# QCopterFC_LED_Sch.net
KiCad netlist of a schematic drawn in Altium Designer
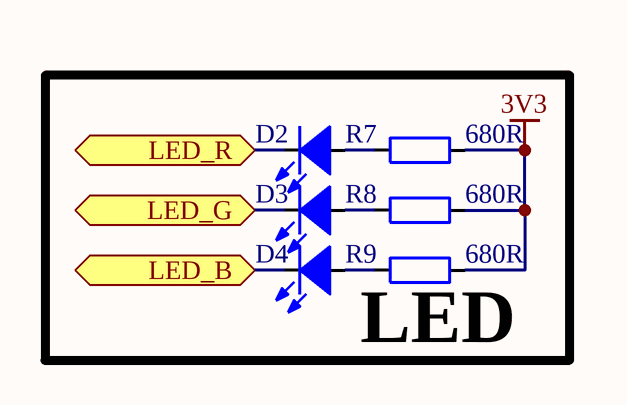
[diagram p0: QCopterFC_LED_Sch.SchDoc]

(export (version "E")
  (design (tool "Eeschema 10.0.6"))
  (components
    (comp (ref "D2")
      (value "LED_0603")
      (footprint "PCB_Active:LED_0603_RED")
      (description "LED")
      (libsource (lib "SCH_Active") (part "LED_0603"))
    )
    (comp (ref "D3")
      (value "LED_0603")
      (footprint "PCB_Active:LED_0603_GREEN")
      (description "LED")
      (libsource (lib "SCH_Active") (part "LED_0603"))
    )
    (comp (ref "D4")
      (value "LED_0603")
      (footprint "PCB_Active:LED_0603_BLUE")
      (description "LED")
      (libsource (lib "SCH_Active") (part "LED_0603"))
    )
    (comp (ref "R7")
      (value "680R")
      (footprint "PCB_Passive:RES_0603")
      (description "Resistor")
      (fields (field (name "Comment") "Res_0603"))
      (libsource (lib "SCH_Passive") (part "Res_0603"))
    )
    (comp (ref "R8")
      (value "680R")
      (footprint "PCB_Passive:RES_0603")
      (description "Resistor")
      (fields (field (name "Comment") "Res_0603"))
      (libsource (lib "SCH_Passive") (part "Res_0603"))
    )
    (comp (ref "R9")
      (value "680R")
      (footprint "PCB_Passive:RES_0603")
      (description "Resistor")
      (fields (field (name "Comment") "Res_0603"))
      (libsource (lib "SCH_Passive") (part "Res_0603"))
    )
  )
  (nets
    (net (code "1") (name "/LED_B") (class "Default")
      (node (ref "D4") (pin "2") (pinfunction "K_2") (pintype "passive"))
    )
    (net (code "2") (name "/LED_G") (class "Default")
      (node (ref "D3") (pin "2") (pinfunction "K_2") (pintype "passive"))
    )
    (net (code "3") (name "/LED_R") (class "Default")
      (node (ref "D2") (pin "2") (pinfunction "K_2") (pintype "passive"))
    )
    (net (code "4") (name "3V3") (class "Default")
      (node (ref "R7") (pin "1") (pinfunction "1_1") (pintype "passive"))
      (node (ref "R8") (pin "1") (pinfunction "1_1") (pintype "passive"))
      (node (ref "R9") (pin "1") (pinfunction "1_1") (pintype "passive"))
    )
    (net (code "5") (name "Net-(D2-A)") (class "Default")
      (node (ref "D2") (pin "1") (pinfunction "A_1") (pintype "passive"))
      (node (ref "R7") (pin "2") (pinfunction "2_2") (pintype "passive"))
    )
    (net (code "6") (name "Net-(D3-A)") (class "Default")
      (node (ref "D3") (pin "1") (pinfunction "A_1") (pintype "passive"))
      (node (ref "R8") (pin "2") (pinfunction "2_2") (pintype "passive"))
    )
    (net (code "7") (name "Net-(D4-A)") (class "Default")
      (node (ref "D4") (pin "1") (pinfunction "A_1") (pintype "passive"))
      (node (ref "R9") (pin "2") (pinfunction "2_2") (pintype "passive"))
    )
  )
)
